# SAMD11_Feather_24QFN.net
KiCad netlist of a schematic drawn in EAGLE
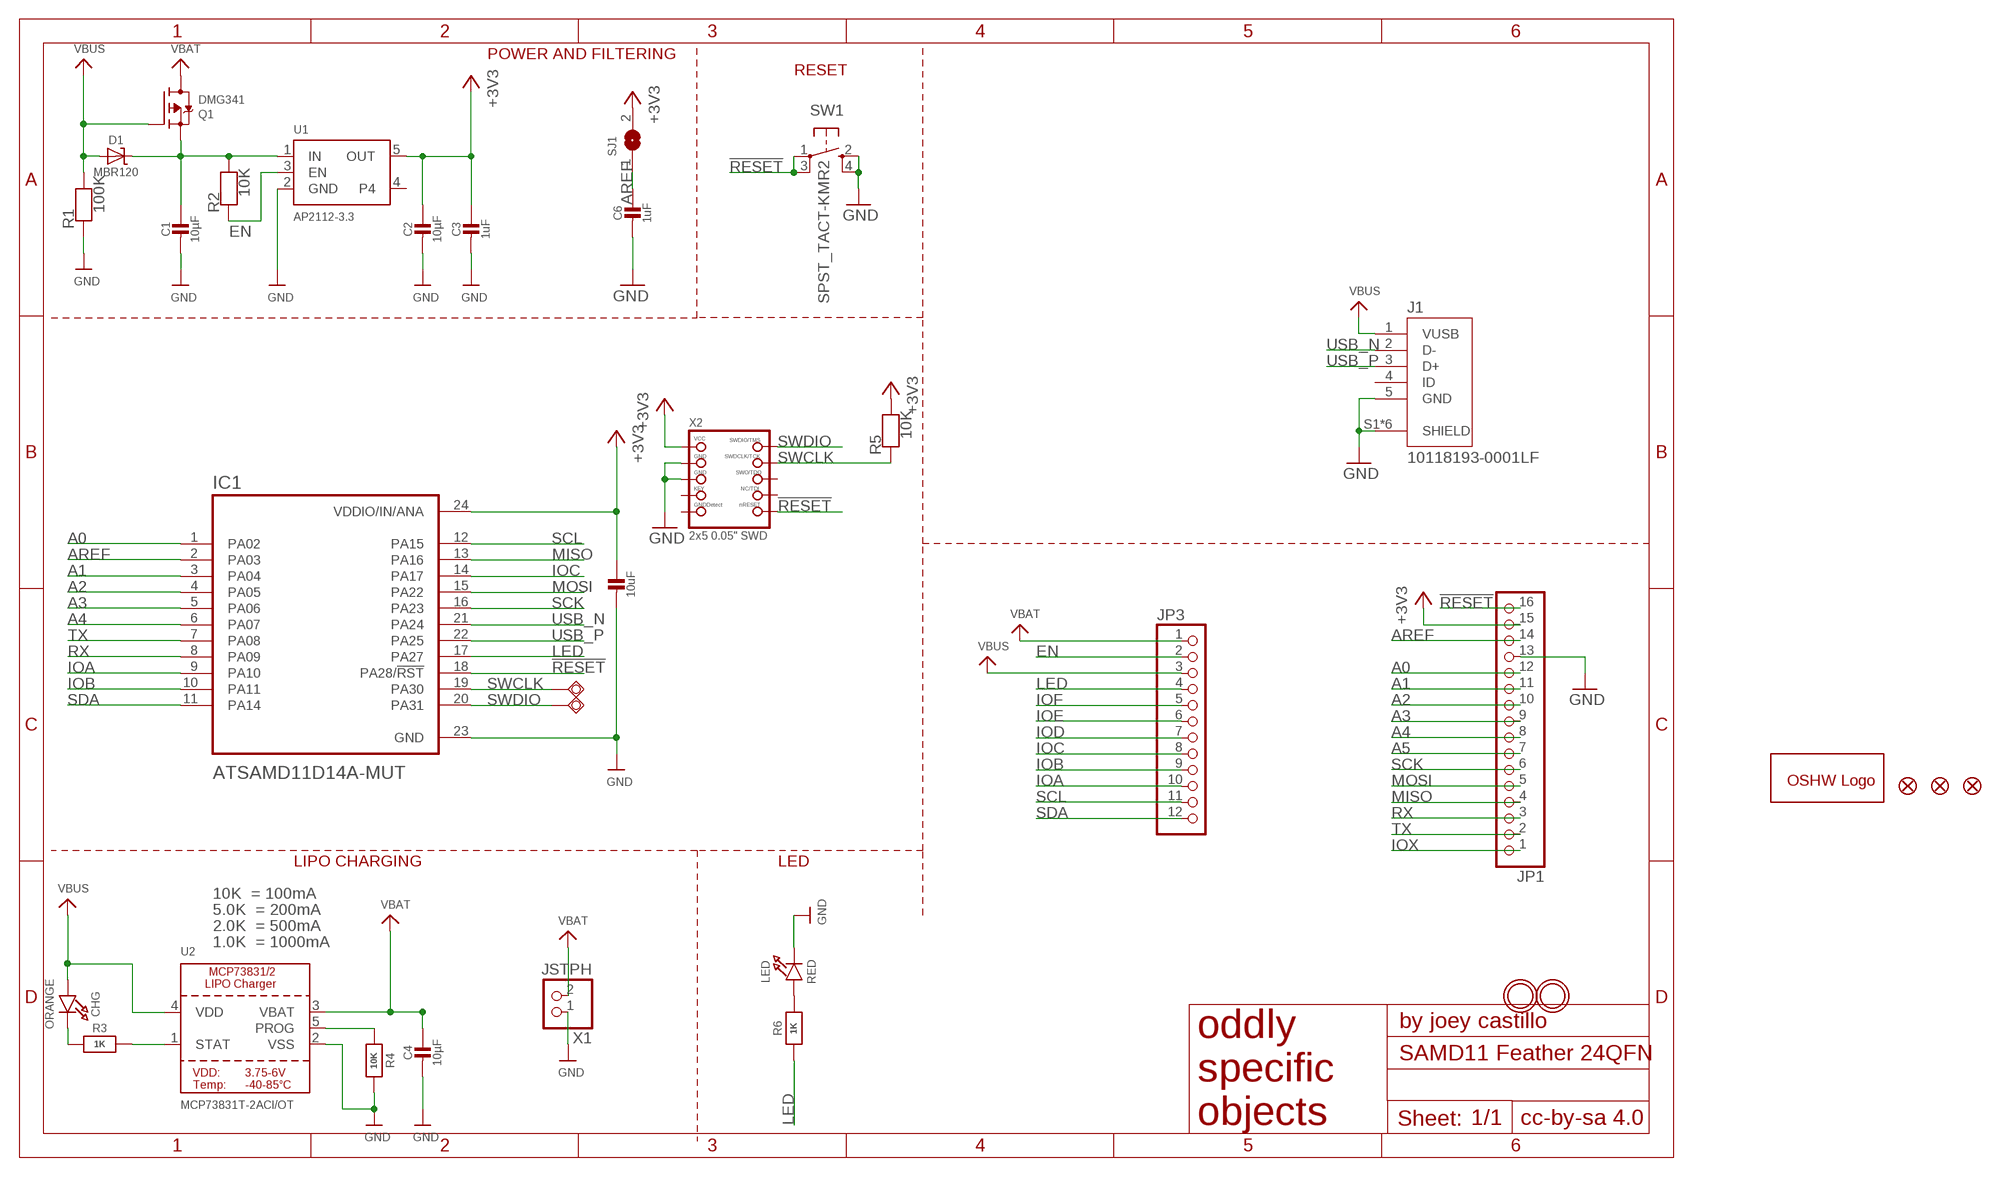
[diagram p0: schematic, sheet 1]

(export (version "E")
  (design (tool "Eeschema 10.0.6"))
  (components
    (comp (ref "C1")
      (value "10µF")
      (footprint "eagle-import:0805-NO")
      (libsource (lib "eagle-import") (part "CAP_CERAMIC0805-NOOUTLINE"))
    )
    (comp (ref "C2")
      (value "10µF")
      (footprint "eagle-import:0805-NO")
      (libsource (lib "eagle-import") (part "CAP_CERAMIC0805-NOOUTLINE"))
    )
    (comp (ref "C3")
      (value "1uF")
      (footprint "eagle-import:0805-NO")
      (libsource (lib "eagle-import") (part "CAP_CERAMIC0805-NOOUTLINE"))
    )
    (comp (ref "C4")
      (value "10µF")
      (footprint "eagle-import:0805-NO")
      (libsource (lib "eagle-import") (part "CAP_CERAMIC0805-NOOUTLINE"))
    )
    (comp (ref "C5")
      (value "10uF")
      (footprint "eagle-import:0805-NO")
      (libsource (lib "eagle-import") (part "CAP_CERAMIC0805-NOOUTLINE"))
    )
    (comp (ref "C6")
      (value "1uF")
      (footprint "eagle-import:0805-NO")
      (libsource (lib "eagle-import") (part "CAP_CERAMIC0805-NOOUTLINE"))
    )
    (comp (ref "CHG")
      (value "ORANGE")
      (footprint "eagle-import:CHIPLED_0805_NOOUTLINE")
      (libsource (lib "eagle-import") (part "LED0805_NOOUTLINE"))
    )
    (comp (ref "D1")
      (value "MBR120")
      (footprint "eagle-import:SOD-123")
      (libsource (lib "eagle-import") (part "DIODE-SCHOTTKYSOD-123"))
    )
    (comp (ref "FID1")
      (value "FIDUCIAL_1MM")
      (footprint "eagle-import:FIDUCIAL_1MM")
      (libsource (lib "eagle-import") (part "FIDUCIAL_1MM"))
    )
    (comp (ref "FID3")
      (value "FIDUCIAL_1MM")
      (footprint "eagle-import:FIDUCIAL_1MM")
      (libsource (lib "eagle-import") (part "FIDUCIAL_1MM"))
    )
    (comp (ref "FID4")
      (value "FIDUCIAL_1MM")
      (footprint "eagle-import:FIDUCIAL_1MM")
      (libsource (lib "eagle-import") (part "FIDUCIAL_1MM"))
    )
    (comp (ref "GOLD_ORB_SM1")
      (value "OSHWLOGOLOGO5MM")
      (footprint "eagle-import:OSHW_5MM")
      (libsource (lib "eagle-import") (part "OSHWLOGOLOGO5MM"))
    )
    (comp (ref "IC1")
      (value "ATSAMD11D14A-MUT")
      (footprint "eagle-import:QFN50P400X400X90-25N")
      (fields (field (name "MF") "Microchip"))
      (libsource (lib "eagle-import") (part "ATSAMD11D14A-MUT"))
    )
    (comp (ref "J1")
      (value "10118193-0001LF")
      (footprint "eagle-import:FCI_10118193-0001LF")
      (fields (field (name "DIGI-KEY_PART_NUMBER") "609-4616-1-ND") (field (name "MF") "Amphenol ICC"))
      (libsource (lib "eagle-import") (part "10118193-0001LF"))
    )
    (comp (ref "JP1")
      (value "HEADER-1X16_MIN")
      (footprint "eagle-import:1X16_ROUND_MIN")
      (libsource (lib "eagle-import") (part "HEADER-1X16_MIN"))
    )
    (comp (ref "JP3")
      (value "HEADER-1X12_MIN")
      (footprint "eagle-import:1X12_ROUND_MIN")
      (libsource (lib "eagle-import") (part "HEADER-1X12_MIN"))
    )
    (comp (ref "LED")
      (value "RED")
      (footprint "eagle-import:CHIPLED_0805_NOOUTLINE")
      (libsource (lib "eagle-import") (part "LED0805_NOOUTLINE"))
    )
    (comp (ref "Q1")
      (value "DMG341")
      (footprint "eagle-import:SOT23-R")
      (libsource (lib "eagle-import") (part "MOSFET-P"))
    )
    (comp (ref "R1")
      (value "100K")
      (footprint "eagle-import:0805-NO")
      (libsource (lib "eagle-import") (part "RESISTOR0805_NOOUTLINE"))
    )
    (comp (ref "R2")
      (value "10K")
      (footprint "eagle-import:0805-NO")
      (libsource (lib "eagle-import") (part "RESISTOR0805_NOOUTLINE"))
    )
    (comp (ref "R3")
      (value "1K")
      (footprint "eagle-import:0805-NO")
      (libsource (lib "eagle-import") (part "RESISTOR0805_NOOUTLINE"))
    )
    (comp (ref "R4")
      (value "10K")
      (footprint "eagle-import:0805-NO")
      (libsource (lib "eagle-import") (part "RESISTOR0805_NOOUTLINE"))
    )
    (comp (ref "R5")
      (value "10K")
      (footprint "eagle-import:0805-NO")
      (libsource (lib "eagle-import") (part "RESISTOR0805_NOOUTLINE"))
    )
    (comp (ref "R6")
      (value "1K")
      (footprint "eagle-import:0805-NO")
      (libsource (lib "eagle-import") (part "RESISTOR0805_NOOUTLINE"))
    )
    (comp (ref "SJ1")
      (value "SOLDERJUMPERCLOSED")
      (footprint "eagle-import:SOLDERJUMPER_CLOSEDWIRE")
      (libsource (lib "eagle-import") (part "SOLDERJUMPERCLOSED"))
    )
    (comp (ref "SW1")
      (value "SPST_TACT-KMR2")
      (footprint "eagle-import:KMR2")
      (libsource (lib "eagle-import") (part "SPST_TACT-KMR2"))
    )
    (comp (ref "SWCLK")
      (value "TPSQTP20R")
      (footprint "eagle-import:TP20R")
      (libsource (lib "eagle-import") (part "TPSQTP20R"))
    )
    (comp (ref "SWDIO")
      (value "TPSQTP20R")
      (footprint "eagle-import:TP20R")
      (libsource (lib "eagle-import") (part "TPSQTP20R"))
    )
    (comp (ref "U$31")
      (value "MOUNTINGHOLE2.5")
      (footprint "eagle-import:MOUNTINGHOLE_2.5_PLATED")
      (libsource (lib "eagle-import") (part "MOUNTINGHOLE2.5"))
    )
    (comp (ref "U$32")
      (value "MOUNTINGHOLE2.5")
      (footprint "eagle-import:MOUNTINGHOLE_2.5_PLATED")
      (libsource (lib "eagle-import") (part "MOUNTINGHOLE2.5"))
    )
    (comp (ref "U1")
      (value "AP2112-3.3")
      (footprint "eagle-import:SOT23-5")
      (libsource (lib "eagle-import") (part "VREG_SOT23-5"))
    )
    (comp (ref "U2")
      (value "MCP73831T-2ACI/OT")
      (footprint "eagle-import:SOT23-5")
      (libsource (lib "eagle-import") (part "MCP73831/2"))
    )
    (comp (ref "X1")
      (value "JSTPH")
      (footprint "eagle-import:JSTPH2")
      (libsource (lib "eagle-import") (part "CON_JST_PH_2PIN"))
    )
    (comp (ref "X2")
      (value "2x5 0.05\" SWD")
      (footprint "eagle-import:2X05_1.27MM_BOX_POSTS")
      (libsource (lib "eagle-import") (part "JTAG-CORTEXBOXPOSTS"))
    )
  )
  (nets
    (net (code "1") (name "+3V3") (class "Default")
      (node (ref "C2") (pin "1") (pinfunction "1_1") (pintype "passive"))
      (node (ref "C3") (pin "1") (pinfunction "1_1") (pintype "passive"))
      (node (ref "C5") (pin "1") (pinfunction "1_1") (pintype "passive"))
      (node (ref "IC1") (pin "24") (pinfunction "VDDIO/IN/ANA_24") (pintype "power_in"))
      (node (ref "JP1") (pin "15") (pinfunction "15_15") (pintype "passive"))
      (node (ref "R5") (pin "2") (pinfunction "2_2") (pintype "passive"))
      (node (ref "SJ1") (pin "2") (pinfunction "2_2") (pintype "passive"))
      (node (ref "U1") (pin "5") (pinfunction "OUT_5") (pintype "power_in"))
      (node (ref "X2") (pin "1") (pinfunction "VCC_1") (pintype "power_in"))
    )
    (net (code "2") (name "/A0") (class "Default")
      (node (ref "IC1") (pin "1") (pinfunction "PA02_1") (pintype "bidirectional"))
      (node (ref "JP1") (pin "12") (pinfunction "12_12") (pintype "passive"))
    )
    (net (code "3") (name "/A1") (class "Default")
      (node (ref "IC1") (pin "3") (pinfunction "PA04_3") (pintype "bidirectional"))
      (node (ref "JP1") (pin "11") (pinfunction "11_11") (pintype "passive"))
    )
    (net (code "4") (name "/A2") (class "Default")
      (node (ref "IC1") (pin "4") (pinfunction "PA05_4") (pintype "bidirectional"))
      (node (ref "JP1") (pin "10") (pinfunction "10_10") (pintype "passive"))
    )
    (net (code "5") (name "/A3") (class "Default")
      (node (ref "IC1") (pin "5") (pinfunction "PA06_5") (pintype "bidirectional"))
      (node (ref "JP1") (pin "9") (pinfunction "9_9") (pintype "passive"))
    )
    (net (code "6") (name "/A4") (class "Default")
      (node (ref "IC1") (pin "6") (pinfunction "PA07_6") (pintype "bidirectional"))
      (node (ref "JP1") (pin "8") (pinfunction "8_8") (pintype "passive"))
    )
    (net (code "7") (name "/A5") (class "Default")
      (node (ref "JP1") (pin "7") (pinfunction "7_7") (pintype "passive"))
    )
    (net (code "8") (name "/AREF") (class "Default")
      (node (ref "C6") (pin "1") (pinfunction "1_1") (pintype "passive"))
      (node (ref "IC1") (pin "2") (pinfunction "PA03_2") (pintype "bidirectional"))
      (node (ref "JP1") (pin "14") (pinfunction "14_14") (pintype "passive"))
      (node (ref "SJ1") (pin "1") (pinfunction "1_1") (pintype "passive"))
    )
    (net (code "9") (name "/EN") (class "Default")
      (node (ref "JP3") (pin "2") (pinfunction "2_2") (pintype "passive"))
      (node (ref "R2") (pin "1") (pinfunction "1_1") (pintype "passive"))
      (node (ref "U1") (pin "3") (pinfunction "EN_3") (pintype "input"))
    )
    (net (code "10") (name "/IOA") (class "Default")
      (node (ref "IC1") (pin "9") (pinfunction "PA10_9") (pintype "bidirectional"))
      (node (ref "JP3") (pin "10") (pinfunction "10_10") (pintype "passive"))
    )
    (net (code "11") (name "/IOB") (class "Default")
      (node (ref "IC1") (pin "10") (pinfunction "PA11_10") (pintype "bidirectional"))
      (node (ref "JP3") (pin "9") (pinfunction "9_9") (pintype "passive"))
    )
    (net (code "12") (name "/IOC") (class "Default")
      (node (ref "IC1") (pin "14") (pinfunction "PA17_14") (pintype "bidirectional"))
      (node (ref "JP3") (pin "8") (pinfunction "8_8") (pintype "passive"))
    )
    (net (code "13") (name "/IOD") (class "Default")
      (node (ref "JP3") (pin "7") (pinfunction "7_7") (pintype "passive"))
    )
    (net (code "14") (name "/IOE") (class "Default")
      (node (ref "JP3") (pin "6") (pinfunction "6_6") (pintype "passive"))
    )
    (net (code "15") (name "/IOF") (class "Default")
      (node (ref "JP3") (pin "5") (pinfunction "5_5") (pintype "passive"))
    )
    (net (code "16") (name "/IOX") (class "Default")
      (node (ref "JP1") (pin "1") (pinfunction "1_1") (pintype "passive"))
    )
    (net (code "17") (name "/LED") (class "Default")
      (node (ref "IC1") (pin "17") (pinfunction "PA27_17") (pintype "bidirectional"))
      (node (ref "JP3") (pin "4") (pinfunction "4_4") (pintype "passive"))
      (node (ref "R6") (pin "1") (pinfunction "1_1") (pintype "passive"))
    )
    (net (code "18") (name "/MISO") (class "Default")
      (node (ref "IC1") (pin "13") (pinfunction "PA16_13") (pintype "bidirectional"))
      (node (ref "JP1") (pin "4") (pinfunction "4_4") (pintype "passive"))
    )
    (net (code "19") (name "/MOSI") (class "Default")
      (node (ref "IC1") (pin "15") (pinfunction "PA22_15") (pintype "bidirectional"))
      (node (ref "JP1") (pin "5") (pinfunction "5_5") (pintype "passive"))
    )
    (net (code "20") (name "/RX") (class "Default")
      (node (ref "IC1") (pin "8") (pinfunction "PA09_8") (pintype "bidirectional"))
      (node (ref "JP1") (pin "3") (pinfunction "3_3") (pintype "passive"))
    )
    (net (code "21") (name "/SCK") (class "Default")
      (node (ref "IC1") (pin "16") (pinfunction "PA23_16") (pintype "bidirectional"))
      (node (ref "JP1") (pin "6") (pinfunction "6_6") (pintype "passive"))
    )
    (net (code "22") (name "/SCL") (class "Default")
      (node (ref "IC1") (pin "12") (pinfunction "PA15_12") (pintype "bidirectional"))
      (node (ref "JP3") (pin "11") (pinfunction "11_11") (pintype "passive"))
    )
    (net (code "23") (name "/SDA") (class "Default")
      (node (ref "IC1") (pin "11") (pinfunction "PA14_11") (pintype "bidirectional"))
      (node (ref "JP3") (pin "12") (pinfunction "12_12") (pintype "passive"))
    )
    (net (code "24") (name "/SWCLK") (class "Default")
      (node (ref "IC1") (pin "19") (pinfunction "PA30_19") (pintype "bidirectional"))
      (node (ref "R5") (pin "1") (pinfunction "1_1") (pintype "passive"))
      (node (ref "SWCLK") (pin "TP") (pinfunction "TP_TP") (pintype "input"))
      (node (ref "X2") (pin "4") (pinfunction "SWDCLK_4") (pintype "bidirectional"))
    )
    (net (code "25") (name "/SWDIO") (class "Default")
      (node (ref "IC1") (pin "20") (pinfunction "PA31_20") (pintype "bidirectional"))
      (node (ref "SWDIO") (pin "TP") (pinfunction "TP_TP") (pintype "input"))
      (node (ref "X2") (pin "2") (pinfunction "SWDIO_2") (pintype "bidirectional"))
    )
    (net (code "26") (name "/TX") (class "Default")
      (node (ref "IC1") (pin "7") (pinfunction "PA08_7") (pintype "bidirectional"))
      (node (ref "JP1") (pin "2") (pinfunction "2_2") (pintype "passive"))
    )
    (net (code "27") (name "/USB_N") (class "Default")
      (node (ref "IC1") (pin "21") (pinfunction "PA24_21") (pintype "bidirectional"))
      (node (ref "J1") (pin "2") (pinfunction "D-_2") (pintype "passive"))
    )
    (net (code "28") (name "/USB_P") (class "Default")
      (node (ref "IC1") (pin "22") (pinfunction "PA25_22") (pintype "bidirectional"))
      (node (ref "J1") (pin "3") (pinfunction "D+_3") (pintype "passive"))
    )
    (net (code "29") (name "/~{RESET}") (class "Default")
      (node (ref "IC1") (pin "18") (pinfunction "PA28/~{RST}_18") (pintype "bidirectional"))
      (node (ref "JP1") (pin "16") (pinfunction "16_16") (pintype "passive"))
      (node (ref "SW1") (pin "1") (pinfunction "P_1") (pintype "passive"))
      (node (ref "SW1") (pin "3") (pinfunction "P1_3") (pintype "passive"))
      (node (ref "X2") (pin "10") (pinfunction "NRESET_10") (pintype "bidirectional"))
    )
    (net (code "30") (name "GND") (class "Default")
      (node (ref "C1") (pin "2") (pinfunction "2_2") (pintype "passive"))
      (node (ref "C2") (pin "2") (pinfunction "2_2") (pintype "passive"))
      (node (ref "C3") (pin "2") (pinfunction "2_2") (pintype "passive"))
      (node (ref "C4") (pin "2") (pinfunction "2_2") (pintype "passive"))
      (node (ref "C5") (pin "2") (pinfunction "2_2") (pintype "passive"))
      (node (ref "C6") (pin "2") (pinfunction "2_2") (pintype "passive"))
      (node (ref "IC1") (pin "23") (pinfunction "GND_23") (pintype "power_in"))
      (node (ref "J1") (pin "5") (pinfunction "GND_5") (pintype "passive"))
      (node (ref "J1") (pin "S1") (pinfunction "SHIELD_S1") (pintype "passive"))
      (node (ref "J1") (pin "S2") (pinfunction "SHIELD_S2") (pintype "passive"))
      (node (ref "J1") (pin "S3") (pinfunction "SHIELD_S3") (pintype "passive"))
      (node (ref "J1") (pin "S4") (pinfunction "SHIELD_S4") (pintype "passive"))
      (node (ref "J1") (pin "S5") (pinfunction "SHIELD_S5") (pintype "passive"))
      (node (ref "J1") (pin "S6") (pinfunction "SHIELD_S6") (pintype "passive"))
      (node (ref "JP1") (pin "13") (pinfunction "13_13") (pintype "passive"))
      (node (ref "LED") (pin "C") (pinfunction "C_C") (pintype "passive"))
      (node (ref "R1") (pin "1") (pinfunction "1_1") (pintype "passive"))
      (node (ref "R4") (pin "2") (pinfunction "2_2") (pintype "passive"))
      (node (ref "SW1") (pin "2") (pinfunction "S_2") (pintype "passive"))
      (node (ref "SW1") (pin "4") (pinfunction "S1_4") (pintype "passive"))
      (node (ref "U1") (pin "2") (pinfunction "GND_2") (pintype "power_in"))
      (node (ref "U2") (pin "2") (pinfunction "VSS_2") (pintype "power_in"))
      (node (ref "X1") (pin "1") (pinfunction "1_1") (pintype "passive"))
      (node (ref "X2") (pin "3") (pinfunction "GND_3") (pintype "power_in"))
      (node (ref "X2") (pin "5") (pinfunction "GND_5") (pintype "power_in"))
    )
    (net (code "31") (name "Net-(CHG-PadC)") (class "Default")
      (node (ref "CHG") (pin "C") (pinfunction "C_C") (pintype "passive"))
      (node (ref "R3") (pin "1") (pinfunction "1_1") (pintype "passive"))
    )
    (net (code "32") (name "Net-(LED-PadA)") (class "Default")
      (node (ref "LED") (pin "A") (pinfunction "A_A") (pintype "passive"))
      (node (ref "R6") (pin "2") (pinfunction "2_2") (pintype "passive"))
    )
    (net (code "33") (name "Net-(Q1-S)") (class "Default")
      (node (ref "C1") (pin "1") (pinfunction "1_1") (pintype "passive"))
      (node (ref "D1") (pin "C") (pinfunction "C_C") (pintype "passive"))
      (node (ref "Q1") (pin "2") (pinfunction "S_2") (pintype "passive"))
      (node (ref "R2") (pin "2") (pinfunction "2_2") (pintype "passive"))
      (node (ref "U1") (pin "1") (pinfunction "IN_1") (pintype "power_in"))
    )
    (net (code "34") (name "Net-(U2-PROG)") (class "Default")
      (node (ref "R4") (pin "1") (pinfunction "1_1") (pintype "passive"))
      (node (ref "U2") (pin "5") (pinfunction "PROG_5") (pintype "input"))
    )
    (net (code "35") (name "Net-(U2-STAT)") (class "Default")
      (node (ref "R3") (pin "2") (pinfunction "2_2") (pintype "passive"))
      (node (ref "U2") (pin "1") (pinfunction "STAT_1") (pintype "output"))
    )
    (net (code "36") (name "VBAT") (class "Default")
      (node (ref "C4") (pin "1") (pinfunction "1_1") (pintype "passive"))
      (node (ref "JP3") (pin "1") (pinfunction "1_1") (pintype "passive"))
      (node (ref "Q1") (pin "3") (pinfunction "D_3") (pintype "passive"))
      (node (ref "U2") (pin "3") (pinfunction "VBAT_3") (pintype "power_in"))
      (node (ref "X1") (pin "2") (pinfunction "2_2") (pintype "passive"))
    )
    (net (code "37") (name "VBUS") (class "Default")
      (node (ref "CHG") (pin "A") (pinfunction "A_A") (pintype "passive"))
      (node (ref "D1") (pin "A") (pinfunction "A_A") (pintype "passive"))
      (node (ref "J1") (pin "1") (pinfunction "VUSB_1") (pintype "passive"))
      (node (ref "JP3") (pin "3") (pinfunction "3_3") (pintype "passive"))
      (node (ref "Q1") (pin "1") (pinfunction "G_1") (pintype "passive"))
      (node (ref "R1") (pin "2") (pinfunction "2_2") (pintype "passive"))
      (node (ref "U2") (pin "4") (pinfunction "VDD_4") (pintype "power_in"))
    )
    (net (code "38") (name "unconnected-(J1-ID-Pad4)") (class "Default")
      (node (ref "J1") (pin "4") (pinfunction "ID_4") (pintype "passive"))
    )
    (net (code "39") (name "unconnected-(U1-P4-Pad4)") (class "Default")
      (node (ref "U1") (pin "4") (pinfunction "P4_4") (pintype "bidirectional"))
    )
    (net (code "40") (name "unconnected-(X2-GNDDETECT-Pad9)") (class "Default")
      (node (ref "X2") (pin "9") (pinfunction "GNDDETECT_9") (pintype "bidirectional"))
    )
    (net (code "41") (name "unconnected-(X2-KEY-Pad7)") (class "Default")
      (node (ref "X2") (pin "7") (pinfunction "KEY_7") (pintype "bidirectional"))
    )
    (net (code "42") (name "unconnected-(X2-SWO-Pad6)") (class "Default")
      (node (ref "X2") (pin "6") (pinfunction "SWO_6") (pintype "bidirectional"))
    )
    (net (code "43") (name "unconnected-(X2-TDI-Pad8)") (class "Default")
      (node (ref "X2") (pin "8") (pinfunction "TDI_8") (pintype "bidirectional"))
    )
  )
)
